# GPIOExpander.net
KiCad netlist of a schematic drawn in Altium Designer
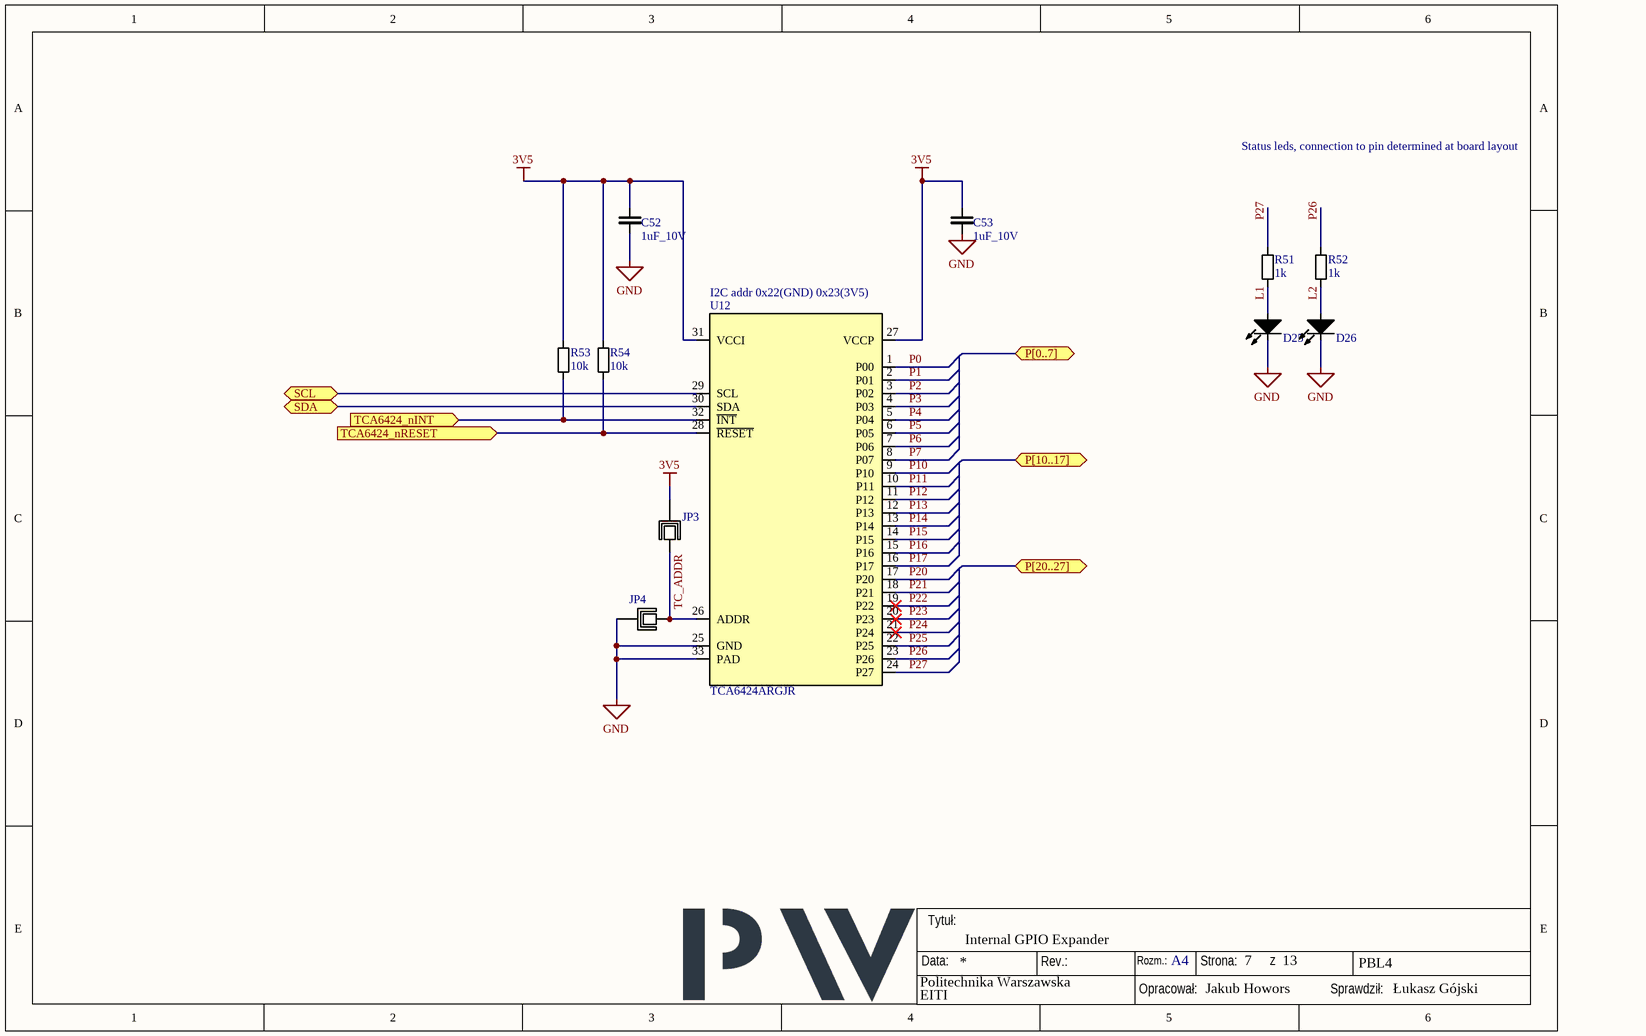
[diagram p0: GPIOExpander.SchDoc]

(export (version "E")
  (design (tool "Eeschema 10.0.6"))
  (components
    (comp (ref "C52")
      (value "1uF_10V")
      (footprint "C_0603")
      (description "Ceramic capacitor")
      (fields (field (name "VOLTAGE") "10V") (field (name "TOLERANCE") "10%"))
      (libsource (lib "Common") (part "C_1uF_10V"))
    )
    (comp (ref "C53")
      (value "1uF_10V")
      (footprint "C_0603")
      (description "Ceramic capacitor")
      (fields (field (name "VOLTAGE") "10V") (field (name "TOLERANCE") "10%"))
      (libsource (lib "Common") (part "C_1uF_10V"))
    )
    (comp (ref "D25")
      (value "RED")
      (footprint "LED_0603")
      (description "LED RED 0603 3.3V")
      (libsource (lib "Common") (part "LED_0603"))
    )
    (comp (ref "D26")
      (value "RED")
      (footprint "LED_0603")
      (description "LED RED 0603 3.3V")
      (libsource (lib "Common") (part "LED_0603"))
    )
    (comp (ref "JP3")
      (value "JUMPER")
      (footprint "Jumper")
      (description "Jumper on traces")
      (libsource (lib "Common") (part "Jumper x2"))
    )
    (comp (ref "JP4")
      (value "JUMPER")
      (footprint "Jumper")
      (description "Jumper on traces")
      (libsource (lib "Common") (part "Jumper x2"))
    )
    (comp (ref "R51")
      (value "1k")
      (footprint "R_0603")
      (description "Resistor")
      (fields (field (name "TOLERANCE") "1%") (field (name "POWER") "100mW"))
      (libsource (lib "Common") (part "R_1k"))
    )
    (comp (ref "R52")
      (value "1k")
      (footprint "R_0603")
      (description "Resistor")
      (fields (field (name "TOLERANCE") "1%") (field (name "POWER") "100mW"))
      (libsource (lib "Common") (part "R_1k"))
    )
    (comp (ref "R53")
      (value "10k")
      (footprint "R_0603")
      (description "Resistor")
      (fields (field (name "TOLERANCE") "1%") (field (name "POWER") "100mW"))
      (libsource (lib "Common") (part "R_10k"))
    )
    (comp (ref "R54")
      (value "10k")
      (footprint "R_0603")
      (description "Resistor")
      (fields (field (name "TOLERANCE") "1%") (field (name "POWER") "100mW"))
      (libsource (lib "Common") (part "R_10k"))
    )
    (comp (ref "U12")
      (value "TCA6424ARGJR")
      (footprint "TCA6424A_RGJ0032A")
      (fields (field (name "MANUFACTURER") "Texas Instruments"))
      (libsource (lib "IOLib") (part "IC_tca6424a_TCA6424ARGJR"))
    )
  )
  (nets
    (net (code "1") (name "/L1") (class "Default")
      (node (ref "D25") (pin "A") (pinfunction "A_A") (pintype "passive"))
      (node (ref "R51") (pin "1") (pinfunction "1_1") (pintype "passive"))
    )
    (net (code "2") (name "/L2") (class "Default")
      (node (ref "D26") (pin "A") (pinfunction "A_A") (pintype "passive"))
      (node (ref "R52") (pin "1") (pinfunction "1_1") (pintype "passive"))
    )
    (net (code "3") (name "/P0") (class "Default")
      (node (ref "U12") (pin "1") (pinfunction "P00_1") (pintype "passive"))
    )
    (net (code "4") (name "/P1") (class "Default")
      (node (ref "U12") (pin "2") (pinfunction "P01_2") (pintype "passive"))
    )
    (net (code "5") (name "/P2") (class "Default")
      (node (ref "U12") (pin "3") (pinfunction "P02_3") (pintype "passive"))
    )
    (net (code "6") (name "/P3") (class "Default")
      (node (ref "U12") (pin "4") (pinfunction "P03_4") (pintype "passive"))
    )
    (net (code "7") (name "/P4") (class "Default")
      (node (ref "U12") (pin "5") (pinfunction "P04_5") (pintype "passive"))
    )
    (net (code "8") (name "/P5") (class "Default")
      (node (ref "U12") (pin "6") (pinfunction "P05_6") (pintype "passive"))
    )
    (net (code "9") (name "/P6") (class "Default")
      (node (ref "U12") (pin "7") (pinfunction "P06_7") (pintype "passive"))
    )
    (net (code "10") (name "/P7") (class "Default")
      (node (ref "U12") (pin "8") (pinfunction "P07_8") (pintype "passive"))
    )
    (net (code "11") (name "/P10") (class "Default")
      (node (ref "U12") (pin "9") (pinfunction "P10_9") (pintype "passive"))
    )
    (net (code "12") (name "/P11") (class "Default")
      (node (ref "U12") (pin "10") (pinfunction "P11_10") (pintype "passive"))
    )
    (net (code "13") (name "/P12") (class "Default")
      (node (ref "U12") (pin "11") (pinfunction "P12_11") (pintype "passive"))
    )
    (net (code "14") (name "/P13") (class "Default")
      (node (ref "U12") (pin "12") (pinfunction "P13_12") (pintype "passive"))
    )
    (net (code "15") (name "/P14") (class "Default")
      (node (ref "U12") (pin "13") (pinfunction "P14_13") (pintype "passive"))
    )
    (net (code "16") (name "/P15") (class "Default")
      (node (ref "U12") (pin "14") (pinfunction "P15_14") (pintype "passive"))
    )
    (net (code "17") (name "/P16") (class "Default")
      (node (ref "U12") (pin "15") (pinfunction "P16_15") (pintype "passive"))
    )
    (net (code "18") (name "/P17") (class "Default")
      (node (ref "U12") (pin "16") (pinfunction "P17_16") (pintype "passive"))
    )
    (net (code "19") (name "/P20") (class "Default")
      (node (ref "U12") (pin "17") (pinfunction "P20_17") (pintype "passive"))
    )
    (net (code "20") (name "/P21") (class "Default")
      (node (ref "U12") (pin "18") (pinfunction "P21_18") (pintype "passive"))
    )
    (net (code "21") (name "/P22") (class "Default")
      (node (ref "U12") (pin "19") (pinfunction "P22_19") (pintype "passive+no_connect"))
    )
    (net (code "22") (name "/P23") (class "Default")
      (node (ref "U12") (pin "20") (pinfunction "P23_20") (pintype "passive+no_connect"))
    )
    (net (code "23") (name "/P24") (class "Default")
      (node (ref "U12") (pin "21") (pinfunction "P24_21") (pintype "passive+no_connect"))
    )
    (net (code "24") (name "/P25") (class "Default")
      (node (ref "U12") (pin "22") (pinfunction "P25_22") (pintype "passive"))
    )
    (net (code "25") (name "/P26") (class "Default")
      (node (ref "R52") (pin "2") (pinfunction "2_2") (pintype "passive"))
      (node (ref "U12") (pin "23") (pinfunction "P26_23") (pintype "passive"))
    )
    (net (code "26") (name "/P27") (class "Default")
      (node (ref "R51") (pin "2") (pinfunction "2_2") (pintype "passive"))
      (node (ref "U12") (pin "24") (pinfunction "P27_24") (pintype "passive"))
    )
    (net (code "30") (name "/SCL") (class "Default")
      (node (ref "U12") (pin "29") (pinfunction "SCL_29") (pintype "passive"))
    )
    (net (code "31") (name "/SDA") (class "Default")
      (node (ref "U12") (pin "30") (pinfunction "SDA_30") (pintype "passive"))
    )
    (net (code "32") (name "/TCA6424_nINT") (class "Default")
      (node (ref "R53") (pin "1") (pinfunction "1_1") (pintype "passive"))
      (node (ref "U12") (pin "32") (pinfunction "~{INT}_32") (pintype "passive"))
    )
    (net (code "33") (name "/TCA6424_nRESET") (class "Default")
      (node (ref "R54") (pin "1") (pinfunction "1_1") (pintype "passive"))
      (node (ref "U12") (pin "28") (pinfunction "~{RESET}_28") (pintype "passive"))
    )
    (net (code "34") (name "/TC_ADDR") (class "Default")
      (node (ref "JP3") (pin "1") (pinfunction "1_1") (pintype "passive"))
      (node (ref "JP4") (pin "1") (pinfunction "1_1") (pintype "passive"))
      (node (ref "U12") (pin "26") (pinfunction "ADDR_26") (pintype "passive"))
    )
    (net (code "35") (name "3V5") (class "Default")
      (node (ref "C52") (pin "2") (pinfunction "2_2") (pintype "passive"))
      (node (ref "C53") (pin "2") (pinfunction "2_2") (pintype "passive"))
      (node (ref "JP3") (pin "2") (pinfunction "2_2") (pintype "passive"))
      (node (ref "R53") (pin "2") (pinfunction "2_2") (pintype "passive"))
      (node (ref "R54") (pin "2") (pinfunction "2_2") (pintype "passive"))
      (node (ref "U12") (pin "27") (pinfunction "VCCP_27") (pintype "passive"))
      (node (ref "U12") (pin "31") (pinfunction "VCCI_31") (pintype "passive"))
    )
    (net (code "36") (name "GND") (class "Default")
      (node (ref "C52") (pin "1") (pinfunction "1_1") (pintype "passive"))
      (node (ref "C53") (pin "1") (pinfunction "1_1") (pintype "passive"))
      (node (ref "D25") (pin "K") (pinfunction "K_K") (pintype "passive"))
      (node (ref "D26") (pin "K") (pinfunction "K_K") (pintype "passive"))
      (node (ref "JP4") (pin "2") (pinfunction "2_2") (pintype "passive"))
      (node (ref "U12") (pin "25") (pinfunction "GND_25") (pintype "passive"))
      (node (ref "U12") (pin "33") (pinfunction "PAD_33") (pintype "passive"))
    )
  )
)
